# design.net
KiCad netlist of a schematic drawn in Altium Designer
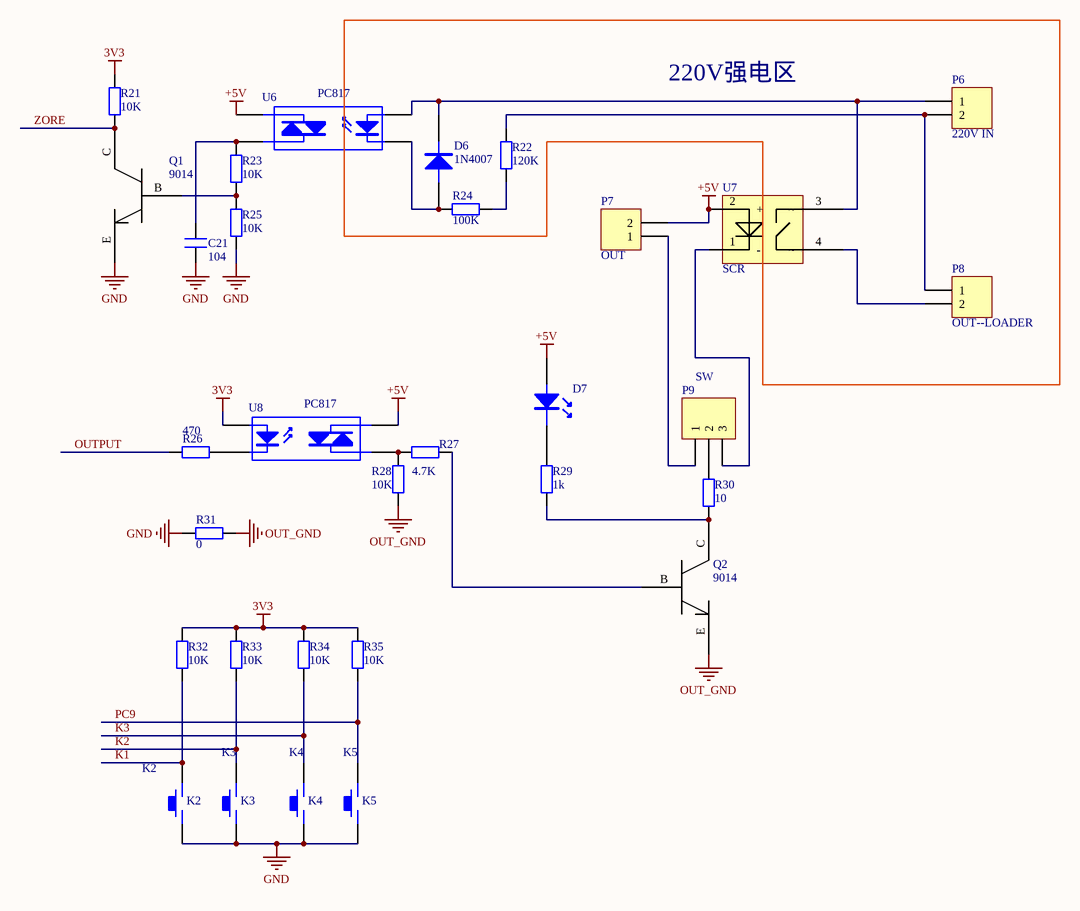
[diagram p0: 输出.SchDoc]

(export (version "E")
  (design (tool "Eeschema 10.0.6"))
  (components
    (comp (ref "C21") (value "104") (footprint "1206") (libsource (lib "MiniSTM32 V3.0封装库") (part "C")))
    (comp (ref "D6")
      (value "1N4007")
      (description "Diode")
      (libsource (lib "Miscellaneous Devices") (part "DIODE"))
    )
    (comp (ref "D7") (value "~") (footprint "李建国1:LED") (libsource (lib "二极管") (part "发光二极管")))
    (comp (ref "K2") (value "K2") (footprint "KEY_M") (libsource (lib "底板封装库") (part "KEY_M")))
    (comp (ref "K3") (value "K3") (footprint "KEY_M") (libsource (lib "底板封装库") (part "KEY_M")))
    (comp (ref "K4") (value "K4") (footprint "KEY_M") (libsource (lib "底板封装库") (part "KEY_M")))
    (comp (ref "K5") (value "K5") (footprint "KEY_M") (libsource (lib "底板封装库") (part "KEY_M")))
    (comp (ref "P6")
      (value "220V IN")
      (footprint "OUT_CJ")
      (description "Header, 2-Pin")
      (fields (field (name "PUBLISHER") "Altium Limited"))
      (libsource (lib "Miscellaneous Connectors") (part "Header 2"))
    )
    (comp (ref "P7")
      (value "OUT")
      (footprint "HDR1X2")
      (description "Header, 2-Pin")
      (fields (field (name "PUBLISHER") "Altium Limited"))
      (libsource (lib "") (part "Header 2_1"))
    )
    (comp (ref "P8")
      (value "OUT--LOADER")
      (footprint "OUT_CJ")
      (description "Header, 2-Pin")
      (fields (field (name "PUBLISHER") "Altium Limited"))
      (libsource (lib "Miscellaneous Connectors") (part "Header 2"))
    )
    (comp (ref "P9")
      (value "SW")
      (footprint "HDR1X3")
      (description "Header, 3-Pin")
      (fields (field (name "PUBLISHER") "Altium Limited"))
      (libsource (lib "Miscellaneous Connectors") (part "Header 3"))
    )
    (comp (ref "Q1") (value "9014") (footprint "9014") (libsource (lib "陈志伟2") (part "9014")))
    (comp (ref "Q2") (value "9014") (footprint "9014") (libsource (lib "陈志伟2") (part "9014")))
    (comp (ref "R21")
      (value "10K")
      (footprint "1206")
      (description "Resistor")
      (fields (field (name "PUBLISHER") "Altium Limited"))
      (libsource (lib "") (part "Res2_1"))
    )
    (comp (ref "R22")
      (value "120K")
      (footprint "1206")
      (description "Resistor")
      (fields (field (name "PUBLISHER") "Altium Limited"))
      (libsource (lib "") (part "Res2_3"))
    )
    (comp (ref "R23")
      (value "10K")
      (footprint "1206")
      (description "Resistor")
      (fields (field (name "PUBLISHER") "Altium Limited"))
      (libsource (lib "") (part "Res2_1"))
    )
    (comp (ref "R24")
      (value "100K")
      (footprint "1206")
      (description "Resistor")
      (fields (field (name "PUBLISHER") "Altium Limited"))
      (libsource (lib "") (part "Res2_2"))
    )
    (comp (ref "R25")
      (value "10K")
      (footprint "1206")
      (description "Resistor")
      (fields (field (name "PUBLISHER") "Altium Limited"))
      (libsource (lib "") (part "Res2_1"))
    )
    (comp (ref "R26")
      (value "470")
      (footprint "1206")
      (description "Resistor")
      (fields (field (name "PUBLISHER") "Altium Limited"))
      (libsource (lib "Miscellaneous Devices") (part "Res2"))
    )
    (comp (ref "R27")
      (value "4.7K")
      (footprint "1206")
      (description "Resistor")
      (fields (field (name "PUBLISHER") "Altium Limited"))
      (libsource (lib "Miscellaneous Devices") (part "Res2"))
    )
    (comp (ref "R28")
      (value "10K")
      (footprint "1206")
      (description "Resistor")
      (fields (field (name "PUBLISHER") "Altium Limited"))
      (libsource (lib "") (part "Res2_1"))
    )
    (comp (ref "R29")
      (value "1k")
      (footprint "1206")
      (description "Resistor")
      (fields (field (name "PUBLISHER") "Altium Limited"))
      (libsource (lib "") (part "Res2_1"))
    )
    (comp (ref "R30")
      (value "10")
      (footprint "1206")
      (description "Resistor")
      (fields (field (name "PUBLISHER") "Altium Limited"))
      (libsource (lib "") (part "Res2_1"))
    )
    (comp (ref "R31")
      (value "0")
      (footprint "1206")
      (description "Resistor")
      (fields (field (name "PUBLISHER") "Altium Limited"))
      (libsource (lib "Miscellaneous Devices") (part "Res2"))
    )
    (comp (ref "R32")
      (value "10K")
      (footprint "1206")
      (description "Resistor")
      (fields (field (name "PUBLISHER") "Altium Limited"))
      (libsource (lib "") (part "Res2_1"))
    )
    (comp (ref "R33")
      (value "10K")
      (footprint "1206")
      (description "Resistor")
      (fields (field (name "PUBLISHER") "Altium Limited"))
      (libsource (lib "") (part "Res2_1"))
    )
    (comp (ref "R34")
      (value "10K")
      (footprint "1206")
      (description "Resistor")
      (fields (field (name "PUBLISHER") "Altium Limited"))
      (libsource (lib "") (part "Res2_1"))
    )
    (comp (ref "R35")
      (value "10K")
      (footprint "1206")
      (description "Resistor")
      (fields (field (name "PUBLISHER") "Altium Limited"))
      (libsource (lib "") (part "Res2_1"))
    )
    (comp (ref "U6")
      (value "PC817")
      (footprint "pc817")
      (libsource (lib "Miscellaneous Devices") (part "OPTOTRIAC"))
    )
    (comp (ref "U7") (value "SCR") (footprint "SCR") (libsource (lib "*") (part "SCR")))
    (comp (ref "U8")
      (value "PC817")
      (footprint "pc817")
      (libsource (lib "Miscellaneous Devices") (part "OPTOTRIAC"))
    )
  )
  (nets
    (net (code "1") (name "+5V") (class "Default")
      (node (ref "D7") (pin "A") (pinfunction "1_A") (pintype "passive"))
      (node (ref "P7") (pin "2") (pinfunction "2_2") (pintype "passive"))
      (node (ref "U6") (pin "3") (pinfunction "A/K_3") (pintype "passive"))
      (node (ref "U7") (pin "2") (pinfunction "+_2") (pintype "passive"))
      (node (ref "U8") (pin "3") (pinfunction "A/K_3") (pintype "passive"))
    )
    (net (code "2") (name "/K1") (class "Default")
      (node (ref "K2") (pin "2") (pinfunction "2_2") (pintype "passive"))
      (node (ref "R32") (pin "1") (pinfunction "1_1") (pintype "passive"))
    )
    (net (code "3") (name "/K2") (class "Default")
      (node (ref "K3") (pin "2") (pinfunction "2_2") (pintype "passive"))
      (node (ref "R33") (pin "1") (pinfunction "1_1") (pintype "passive"))
    )
    (net (code "4") (name "/K3") (class "Default")
      (node (ref "K4") (pin "2") (pinfunction "2_2") (pintype "passive"))
      (node (ref "R34") (pin "1") (pinfunction "1_1") (pintype "passive"))
    )
    (net (code "5") (name "/OUTPUT") (class "Default")
      (node (ref "R26") (pin "2") (pinfunction "2_2") (pintype "passive"))
    )
    (net (code "6") (name "/PC9") (class "Default")
      (node (ref "K5") (pin "2") (pinfunction "2_2") (pintype "passive"))
      (node (ref "R35") (pin "1") (pinfunction "1_1") (pintype "passive"))
    )
    (net (code "7") (name "/ZORE") (class "Default")
      (node (ref "Q1") (pin "C") (pinfunction "C_C") (pintype "passive"))
      (node (ref "R21") (pin "1") (pinfunction "1_1") (pintype "passive"))
    )
    (net (code "8") (name "3V3") (class "Default")
      (node (ref "R21") (pin "2") (pinfunction "2_2") (pintype "passive"))
      (node (ref "R32") (pin "2") (pinfunction "2_2") (pintype "passive"))
      (node (ref "R33") (pin "2") (pinfunction "2_2") (pintype "passive"))
      (node (ref "R34") (pin "2") (pinfunction "2_2") (pintype "passive"))
      (node (ref "R35") (pin "2") (pinfunction "2_2") (pintype "passive"))
      (node (ref "U8") (pin "1") (pinfunction "A_1") (pintype "passive"))
    )
    (net (code "9") (name "GND") (class "Default")
      (node (ref "C21") (pin "2") (pintype "passive"))
      (node (ref "K2") (pin "1") (pinfunction "1_1") (pintype "passive"))
      (node (ref "K3") (pin "1") (pinfunction "1_1") (pintype "passive"))
      (node (ref "K4") (pin "1") (pinfunction "1_1") (pintype "passive"))
      (node (ref "K5") (pin "1") (pinfunction "1_1") (pintype "passive"))
      (node (ref "Q1") (pin "E") (pinfunction "E_E") (pintype "passive"))
      (node (ref "R25") (pin "1") (pinfunction "1_1") (pintype "passive"))
      (node (ref "R31") (pin "2") (pinfunction "2_2") (pintype "passive"))
    )
    (net (code "10") (name "Net-(C21-Pad1)") (class "Default")
      (node (ref "C21") (pin "1") (pintype "passive"))
      (node (ref "R23") (pin "2") (pinfunction "2_2") (pintype "passive"))
      (node (ref "U6") (pin "4") (pinfunction "A/K_4") (pintype "passive"))
    )
    (net (code "11") (name "Net-(D6-A)") (class "Default")
      (node (ref "D6") (pin "1") (pinfunction "A_1") (pintype "passive"))
      (node (ref "R24") (pin "1") (pinfunction "1_1") (pintype "passive"))
      (node (ref "U6") (pin "2") (pinfunction "K_2") (pintype "passive"))
    )
    (net (code "12") (name "Net-(D6-K)") (class "Default")
      (node (ref "D6") (pin "2") (pinfunction "K_2") (pintype "passive"))
      (node (ref "P6") (pin "1") (pinfunction "1_1") (pintype "passive"))
      (node (ref "U6") (pin "1") (pinfunction "A_1") (pintype "passive"))
      (node (ref "U7") (pin "3") (pinfunction "~_3") (pintype "passive"))
    )
    (net (code "13") (name "Net-(D7-2)") (class "Default")
      (node (ref "D7") (pin "K") (pinfunction "2_K") (pintype "passive"))
      (node (ref "R29") (pin "2") (pinfunction "2_2") (pintype "passive"))
    )
    (net (code "14") (name "Net-(P6-Pad2)") (class "Default")
      (node (ref "P6") (pin "2") (pinfunction "2_2") (pintype "passive"))
      (node (ref "P8") (pin "1") (pinfunction "1_1") (pintype "passive"))
      (node (ref "R22") (pin "1") (pinfunction "1_1") (pintype "passive"))
    )
    (net (code "15") (name "Net-(P7-Pad1)") (class "Default")
      (node (ref "P7") (pin "1") (pinfunction "1_1") (pintype "passive"))
      (node (ref "P9") (pin "1") (pinfunction "1_1") (pintype "passive"))
    )
    (net (code "16") (name "Net-(P8-Pad2)") (class "Default")
      (node (ref "P8") (pin "2") (pinfunction "2_2") (pintype "passive"))
      (node (ref "U7") (pin "4") (pinfunction "~_4") (pintype "passive"))
    )
    (net (code "17") (name "Net-(P9-Pad2)") (class "Default")
      (node (ref "P9") (pin "2") (pinfunction "2_2") (pintype "passive"))
      (node (ref "R30") (pin "2") (pinfunction "2_2") (pintype "passive"))
    )
    (net (code "18") (name "Net-(Q1-PadB)") (class "Default")
      (node (ref "Q1") (pin "B") (pinfunction "B_B") (pintype "passive"))
      (node (ref "R23") (pin "1") (pinfunction "1_1") (pintype "passive"))
      (node (ref "R25") (pin "2") (pinfunction "2_2") (pintype "passive"))
    )
    (net (code "19") (name "Net-(Q2-PadB)") (class "Default")
      (node (ref "Q2") (pin "B") (pinfunction "B_B") (pintype "passive"))
      (node (ref "R27") (pin "1") (pinfunction "1_1") (pintype "passive"))
    )
    (net (code "20") (name "Net-(Q2-PadC)") (class "Default")
      (node (ref "Q2") (pin "C") (pinfunction "C_C") (pintype "passive"))
      (node (ref "R29") (pin "1") (pinfunction "1_1") (pintype "passive"))
      (node (ref "R30") (pin "1") (pinfunction "1_1") (pintype "passive"))
    )
    (net (code "21") (name "Net-(R22-Pad2)") (class "Default")
      (node (ref "R22") (pin "2") (pinfunction "2_2") (pintype "passive"))
      (node (ref "R24") (pin "2") (pinfunction "2_2") (pintype "passive"))
    )
    (net (code "22") (name "Net-(R27-Pad2)") (class "Default")
      (node (ref "R27") (pin "2") (pinfunction "2_2") (pintype "passive"))
      (node (ref "R28") (pin "2") (pinfunction "2_2") (pintype "passive"))
      (node (ref "U8") (pin "4") (pinfunction "A/K_4") (pintype "passive"))
    )
    (net (code "23") (name "Net-(U7--)") (class "Default")
      (node (ref "P9") (pin "3") (pinfunction "3_3") (pintype "passive"))
      (node (ref "U7") (pin "1") (pinfunction "-_1") (pintype "passive"))
    )
    (net (code "24") (name "Net-(U8-K)") (class "Default")
      (node (ref "R26") (pin "1") (pinfunction "1_1") (pintype "passive"))
      (node (ref "U8") (pin "2") (pinfunction "K_2") (pintype "passive"))
    )
    (net (code "25") (name "OUT_GND") (class "Default")
      (node (ref "Q2") (pin "E") (pinfunction "E_E") (pintype "passive"))
      (node (ref "R28") (pin "1") (pinfunction "1_1") (pintype "passive"))
      (node (ref "R31") (pin "1") (pinfunction "1_1") (pintype "passive"))
    )
  )
)
